# tsshield.net
KiCad netlist of a schematic drawn in EAGLE
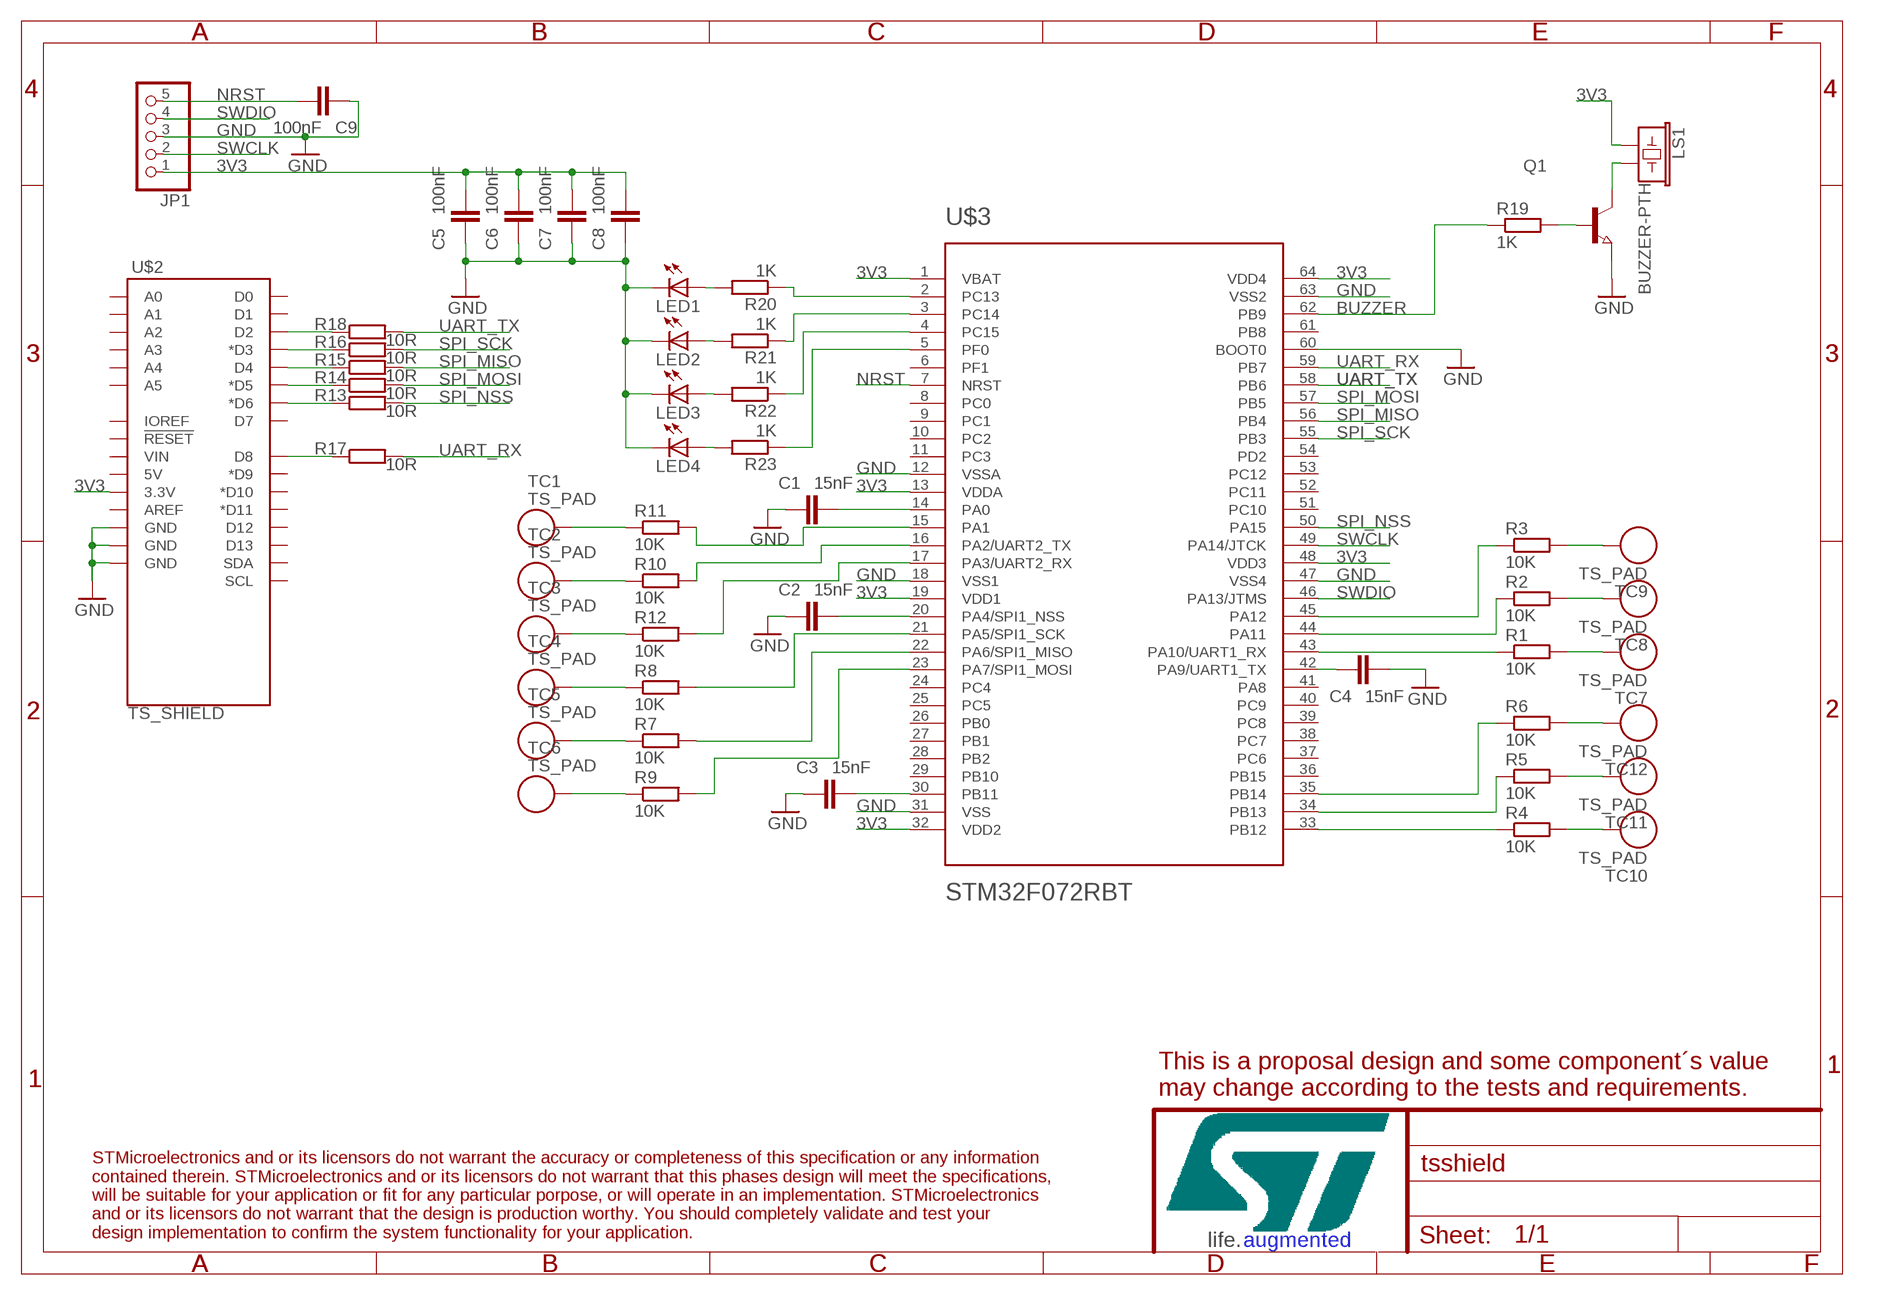
[diagram p0: schematic, sheet 1]

(export (version "E")
  (design (tool "Eeschema 10.0.6"))
  (components
    (comp (ref "C1")
      (value "15nF")
      (footprint "eagle-import:C0603")
      (libsource (lib "eagle-import") (part "CC0603"))
    )
    (comp (ref "C2")
      (value "15nF")
      (footprint "eagle-import:C0603")
      (libsource (lib "eagle-import") (part "CC0603"))
    )
    (comp (ref "C3")
      (value "15nF")
      (footprint "eagle-import:C0603")
      (libsource (lib "eagle-import") (part "CC0603"))
    )
    (comp (ref "C4")
      (value "15nF")
      (footprint "eagle-import:C0603")
      (libsource (lib "eagle-import") (part "CC0603"))
    )
    (comp (ref "C5")
      (value "100nF")
      (footprint "eagle-import:C0603")
      (libsource (lib "eagle-import") (part "CC0603"))
    )
    (comp (ref "C6")
      (value "100nF")
      (footprint "eagle-import:C0603")
      (libsource (lib "eagle-import") (part "CC0603"))
    )
    (comp (ref "C7")
      (value "100nF")
      (footprint "eagle-import:C0603")
      (libsource (lib "eagle-import") (part "CC0603"))
    )
    (comp (ref "C8")
      (value "100nF")
      (footprint "eagle-import:C0603")
      (libsource (lib "eagle-import") (part "CC0603"))
    )
    (comp (ref "C9")
      (value "100nF")
      (footprint "eagle-import:C0603")
      (libsource (lib "eagle-import") (part "CC0603"))
    )
    (comp (ref "JP1")
      (value "PINHD-1X5")
      (footprint "eagle-import:1X05")
      (libsource (lib "eagle-import") (part "PINHD-1X5"))
    )
    (comp (ref "LED1")
      (value "LED_E")
      (footprint "eagle-import:LED_1206")
      (libsource (lib "eagle-import") (part "LED_E"))
    )
    (comp (ref "LED2")
      (value "LED_E")
      (footprint "eagle-import:LED_1206")
      (libsource (lib "eagle-import") (part "LED_E"))
    )
    (comp (ref "LED3")
      (value "LED_E")
      (footprint "eagle-import:LED_1206")
      (libsource (lib "eagle-import") (part "LED_E"))
    )
    (comp (ref "LED4")
      (value "LED_E")
      (footprint "eagle-import:LED_1206")
      (libsource (lib "eagle-import") (part "LED_E"))
    )
    (comp (ref "LS1")
      (value "BUZZER-PTH")
      (footprint "eagle-import:BUZZER-12MM")
      (libsource (lib "eagle-import") (part "BUZZER-PTH"))
    )
    (comp (ref "Q1")
      (value "NPN-TRANSISTOR_SOT23")
      (footprint "eagle-import:SOT23")
      (libsource (lib "eagle-import") (part "NPN-TRANSISTOR_SOT23"))
    )
    (comp (ref "R1")
      (value "10K")
      (footprint "eagle-import:R0603")
      (libsource (lib "eagle-import") (part "RR0603"))
    )
    (comp (ref "R2")
      (value "10K")
      (footprint "eagle-import:R0603")
      (libsource (lib "eagle-import") (part "RR0603"))
    )
    (comp (ref "R3")
      (value "10K")
      (footprint "eagle-import:R0603")
      (libsource (lib "eagle-import") (part "RR0603"))
    )
    (comp (ref "R4")
      (value "10K")
      (footprint "eagle-import:R0603")
      (libsource (lib "eagle-import") (part "RR0603"))
    )
    (comp (ref "R5")
      (value "10K")
      (footprint "eagle-import:R0603")
      (libsource (lib "eagle-import") (part "RR0603"))
    )
    (comp (ref "R6")
      (value "10K")
      (footprint "eagle-import:R0603")
      (libsource (lib "eagle-import") (part "RR0603"))
    )
    (comp (ref "R7")
      (value "10K")
      (footprint "eagle-import:R0603")
      (libsource (lib "eagle-import") (part "RR0603"))
    )
    (comp (ref "R8")
      (value "10K")
      (footprint "eagle-import:R0603")
      (libsource (lib "eagle-import") (part "RR0603"))
    )
    (comp (ref "R9")
      (value "10K")
      (footprint "eagle-import:R0603")
      (libsource (lib "eagle-import") (part "RR0603"))
    )
    (comp (ref "R10")
      (value "10K")
      (footprint "eagle-import:R0603")
      (libsource (lib "eagle-import") (part "RR0603"))
    )
    (comp (ref "R11")
      (value "10K")
      (footprint "eagle-import:R0603")
      (libsource (lib "eagle-import") (part "RR0603"))
    )
    (comp (ref "R12")
      (value "10K")
      (footprint "eagle-import:R0603")
      (libsource (lib "eagle-import") (part "RR0603"))
    )
    (comp (ref "R13")
      (value "10R")
      (footprint "eagle-import:R0603")
      (libsource (lib "eagle-import") (part "RR0603"))
    )
    (comp (ref "R14")
      (value "10R")
      (footprint "eagle-import:R0603")
      (libsource (lib "eagle-import") (part "RR0603"))
    )
    (comp (ref "R15")
      (value "10R")
      (footprint "eagle-import:R0603")
      (libsource (lib "eagle-import") (part "RR0603"))
    )
    (comp (ref "R16")
      (value "10R")
      (footprint "eagle-import:R0603")
      (libsource (lib "eagle-import") (part "RR0603"))
    )
    (comp (ref "R17")
      (value "10R")
      (footprint "eagle-import:R0603")
      (libsource (lib "eagle-import") (part "RR0603"))
    )
    (comp (ref "R18")
      (value "10R")
      (footprint "eagle-import:R0603")
      (libsource (lib "eagle-import") (part "RR0603"))
    )
    (comp (ref "R19")
      (value "1K")
      (footprint "eagle-import:R0603")
      (libsource (lib "eagle-import") (part "RR0603"))
    )
    (comp (ref "R20")
      (value "1K")
      (footprint "eagle-import:R0603")
      (libsource (lib "eagle-import") (part "RR0603"))
    )
    (comp (ref "R21")
      (value "1K")
      (footprint "eagle-import:R0603")
      (libsource (lib "eagle-import") (part "RR0603"))
    )
    (comp (ref "R22")
      (value "1K")
      (footprint "eagle-import:R0603")
      (libsource (lib "eagle-import") (part "RR0603"))
    )
    (comp (ref "R23")
      (value "1K")
      (footprint "eagle-import:R0603")
      (libsource (lib "eagle-import") (part "RR0603"))
    )
    (comp (ref "TC1")
      (value "TS_PAD")
      (footprint "eagle-import:TS_PAD")
      (libsource (lib "eagle-import") (part "TS_PAD"))
    )
    (comp (ref "TC2")
      (value "TS_PAD")
      (footprint "eagle-import:TS_PAD")
      (libsource (lib "eagle-import") (part "TS_PAD"))
    )
    (comp (ref "TC3")
      (value "TS_PAD")
      (footprint "eagle-import:TS_PAD")
      (libsource (lib "eagle-import") (part "TS_PAD"))
    )
    (comp (ref "TC4")
      (value "TS_PAD")
      (footprint "eagle-import:TS_PAD")
      (libsource (lib "eagle-import") (part "TS_PAD"))
    )
    (comp (ref "TC5")
      (value "TS_PAD")
      (footprint "eagle-import:TS_PAD")
      (libsource (lib "eagle-import") (part "TS_PAD"))
    )
    (comp (ref "TC6")
      (value "TS_PAD")
      (footprint "eagle-import:TS_PAD")
      (libsource (lib "eagle-import") (part "TS_PAD"))
    )
    (comp (ref "TC7")
      (value "TS_PAD")
      (footprint "eagle-import:TS_PAD")
      (libsource (lib "eagle-import") (part "TS_PAD"))
    )
    (comp (ref "TC8")
      (value "TS_PAD")
      (footprint "eagle-import:TS_PAD")
      (libsource (lib "eagle-import") (part "TS_PAD"))
    )
    (comp (ref "TC9")
      (value "TS_PAD")
      (footprint "eagle-import:TS_PAD")
      (libsource (lib "eagle-import") (part "TS_PAD"))
    )
    (comp (ref "TC10")
      (value "TS_PAD")
      (footprint "eagle-import:TS_PAD")
      (libsource (lib "eagle-import") (part "TS_PAD"))
    )
    (comp (ref "TC11")
      (value "TS_PAD")
      (footprint "eagle-import:TS_PAD")
      (libsource (lib "eagle-import") (part "TS_PAD"))
    )
    (comp (ref "TC12")
      (value "TS_PAD")
      (footprint "eagle-import:TS_PAD")
      (libsource (lib "eagle-import") (part "TS_PAD"))
    )
    (comp (ref "U$2")
      (value "TS_SHIELD")
      (footprint "eagle-import:TS_SHIELD")
      (libsource (lib "eagle-import") (part "TS_SHIELD"))
    )
    (comp (ref "U$3")
      (value "STM32F072RBT")
      (footprint "eagle-import:TQFP64")
      (libsource (lib "eagle-import") (part "STM32F072RBT"))
    )
  )
  (nets
    (net (code "1") (name "/3V3") (class "Default")
      (node (ref "C5") (pin "1") (pinfunction "1_1") (pintype "passive"))
      (node (ref "C6") (pin "1") (pinfunction "1_1") (pintype "passive"))
      (node (ref "C7") (pin "1") (pinfunction "1_1") (pintype "passive"))
      (node (ref "C8") (pin "1") (pinfunction "1_1") (pintype "passive"))
      (node (ref "JP1") (pin "1") (pinfunction "1_1") (pintype "passive"))
      (node (ref "LS1") (pin "+") (pinfunction "1_+") (pintype "passive"))
      (node (ref "U$2") (pin "3.3V") (pinfunction "3.3V_3.3V") (pintype "bidirectional"))
      (node (ref "U$3") (pin "1") (pinfunction "VBAT_1") (pintype "bidirectional"))
      (node (ref "U$3") (pin "13") (pinfunction "VDDA_13") (pintype "bidirectional"))
      (node (ref "U$3") (pin "19") (pinfunction "VDD1_19") (pintype "bidirectional"))
      (node (ref "U$3") (pin "32") (pinfunction "VDD2_32") (pintype "bidirectional"))
      (node (ref "U$3") (pin "48") (pinfunction "VDD3_48") (pintype "bidirectional"))
      (node (ref "U$3") (pin "64") (pinfunction "VDD4_64") (pintype "bidirectional"))
    )
    (net (code "2") (name "/BUZZER") (class "Default")
      (node (ref "R19") (pin "1") (pinfunction "1_1") (pintype "passive"))
      (node (ref "U$3") (pin "62") (pinfunction "PB9_62") (pintype "bidirectional"))
    )
    (net (code "3") (name "/NRST") (class "Default")
      (node (ref "C9") (pin "1") (pinfunction "1_1") (pintype "passive"))
      (node (ref "JP1") (pin "5") (pinfunction "5_5") (pintype "passive"))
      (node (ref "U$3") (pin "7") (pinfunction "NRST_7") (pintype "bidirectional"))
    )
    (net (code "4") (name "/SPI_MISO") (class "Default")
      (node (ref "R15") (pin "2") (pinfunction "2_2") (pintype "passive"))
      (node (ref "U$3") (pin "56") (pinfunction "PB4_56") (pintype "bidirectional"))
    )
    (net (code "5") (name "/SPI_MOSI") (class "Default")
      (node (ref "R14") (pin "2") (pinfunction "2_2") (pintype "passive"))
      (node (ref "U$3") (pin "57") (pinfunction "PB5_57") (pintype "bidirectional"))
    )
    (net (code "6") (name "/SPI_NSS") (class "Default")
      (node (ref "R13") (pin "2") (pinfunction "2_2") (pintype "passive"))
      (node (ref "U$3") (pin "50") (pinfunction "PA15_50") (pintype "bidirectional"))
    )
    (net (code "7") (name "/SPI_SCK") (class "Default")
      (node (ref "R16") (pin "2") (pinfunction "2_2") (pintype "passive"))
      (node (ref "U$3") (pin "55") (pinfunction "PB3_55") (pintype "bidirectional"))
    )
    (net (code "8") (name "/SWCLK") (class "Default")
      (node (ref "JP1") (pin "2") (pinfunction "2_2") (pintype "passive"))
      (node (ref "U$3") (pin "49") (pinfunction "PA14/JTCK_49") (pintype "bidirectional"))
    )
    (net (code "9") (name "/SWDIO") (class "Default")
      (node (ref "JP1") (pin "4") (pinfunction "4_4") (pintype "passive"))
      (node (ref "U$3") (pin "46") (pinfunction "PA13/JTMS_46") (pintype "bidirectional"))
    )
    (net (code "10") (name "/UART_RX") (class "Default")
      (node (ref "R17") (pin "2") (pinfunction "2_2") (pintype "passive"))
      (node (ref "U$3") (pin "59") (pinfunction "PB7_59") (pintype "bidirectional"))
    )
    (net (code "11") (name "/UART_TX") (class "Default")
      (node (ref "R18") (pin "2") (pinfunction "2_2") (pintype "passive"))
      (node (ref "U$3") (pin "58") (pinfunction "PB6_58") (pintype "bidirectional"))
    )
    (net (code "12") (name "GND") (class "Default")
      (node (ref "C1") (pin "2") (pinfunction "2_2") (pintype "passive"))
      (node (ref "C2") (pin "2") (pinfunction "2_2") (pintype "passive"))
      (node (ref "C3") (pin "2") (pinfunction "2_2") (pintype "passive"))
      (node (ref "C4") (pin "1") (pinfunction "1_1") (pintype "passive"))
      (node (ref "C5") (pin "2") (pinfunction "2_2") (pintype "passive"))
      (node (ref "C6") (pin "2") (pinfunction "2_2") (pintype "passive"))
      (node (ref "C7") (pin "2") (pinfunction "2_2") (pintype "passive"))
      (node (ref "C8") (pin "2") (pinfunction "2_2") (pintype "passive"))
      (node (ref "C9") (pin "2") (pinfunction "2_2") (pintype "passive"))
      (node (ref "JP1") (pin "3") (pinfunction "3_3") (pintype "passive"))
      (node (ref "LED1") (pin "C") (pinfunction "C_C") (pintype "passive"))
      (node (ref "LED2") (pin "C") (pinfunction "C_C") (pintype "passive"))
      (node (ref "LED3") (pin "C") (pinfunction "C_C") (pintype "passive"))
      (node (ref "LED4") (pin "C") (pinfunction "C_C") (pintype "passive"))
      (node (ref "Q1") (pin "2") (pinfunction "E_2") (pintype "passive"))
      (node (ref "U$2") (pin "GND@1") (pinfunction "GND_GND@1") (pintype "bidirectional"))
      (node (ref "U$2") (pin "GND@2") (pinfunction "GND_GND@2") (pintype "bidirectional"))
      (node (ref "U$2") (pin "GND@3") (pinfunction "GND_GND@3") (pintype "bidirectional"))
      (node (ref "U$3") (pin "12") (pinfunction "VSSA_12") (pintype "bidirectional"))
      (node (ref "U$3") (pin "18") (pinfunction "VSS1_18") (pintype "bidirectional"))
      (node (ref "U$3") (pin "31") (pinfunction "VSS_31") (pintype "bidirectional"))
      (node (ref "U$3") (pin "47") (pinfunction "VSS4_47") (pintype "bidirectional"))
      (node (ref "U$3") (pin "60") (pinfunction "BOOT0_60") (pintype "bidirectional"))
      (node (ref "U$3") (pin "63") (pinfunction "VSS2_63") (pintype "bidirectional"))
    )
    (net (code "13") (name "Net-(LED1-PadA)") (class "Default")
      (node (ref "LED1") (pin "A") (pinfunction "A_A") (pintype "passive"))
      (node (ref "R20") (pin "2") (pinfunction "2_2") (pintype "passive"))
    )
    (net (code "14") (name "Net-(LED2-PadA)") (class "Default")
      (node (ref "LED2") (pin "A") (pinfunction "A_A") (pintype "passive"))
      (node (ref "R21") (pin "2") (pinfunction "2_2") (pintype "passive"))
    )
    (net (code "15") (name "Net-(LED3-PadA)") (class "Default")
      (node (ref "LED3") (pin "A") (pinfunction "A_A") (pintype "passive"))
      (node (ref "R22") (pin "2") (pinfunction "2_2") (pintype "passive"))
    )
    (net (code "16") (name "Net-(LED4-PadA)") (class "Default")
      (node (ref "LED4") (pin "A") (pinfunction "A_A") (pintype "passive"))
      (node (ref "R23") (pin "2") (pinfunction "2_2") (pintype "passive"))
    )
    (net (code "17") (name "Net-(LS1-2)") (class "Default")
      (node (ref "LS1") (pin "-") (pinfunction "2_-") (pintype "passive"))
      (node (ref "Q1") (pin "3") (pinfunction "C_3") (pintype "passive"))
    )
    (net (code "18") (name "Net-(Q1-B)") (class "Default")
      (node (ref "Q1") (pin "1") (pinfunction "B_1") (pintype "passive"))
      (node (ref "R19") (pin "2") (pinfunction "2_2") (pintype "passive"))
    )
    (net (code "19") (name "Net-(R15-Pad1)") (class "Default")
      (node (ref "R15") (pin "1") (pinfunction "1_1") (pintype "passive"))
      (node (ref "U$2") (pin "D4") (pinfunction "D4_D4") (pintype "bidirectional"))
    )
    (net (code "20") (name "Net-(R17-Pad1)") (class "Default")
      (node (ref "R17") (pin "1") (pinfunction "1_1") (pintype "passive"))
      (node (ref "U$2") (pin "D8") (pinfunction "D8_D8") (pintype "bidirectional"))
    )
    (net (code "21") (name "Net-(R18-Pad1)") (class "Default")
      (node (ref "R18") (pin "1") (pinfunction "1_1") (pintype "passive"))
      (node (ref "U$2") (pin "D2") (pinfunction "D2_D2") (pintype "bidirectional"))
    )
    (net (code "22") (name "Net-(TC1-P$1)") (class "Default")
      (node (ref "R11") (pin "1") (pinfunction "1_1") (pintype "passive"))
      (node (ref "TC1") (pin "1") (pinfunction "P$1_1") (pintype "bidirectional"))
    )
    (net (code "23") (name "Net-(TC2-P$1)") (class "Default")
      (node (ref "R10") (pin "1") (pinfunction "1_1") (pintype "passive"))
      (node (ref "TC2") (pin "1") (pinfunction "P$1_1") (pintype "bidirectional"))
    )
    (net (code "24") (name "Net-(TC3-P$1)") (class "Default")
      (node (ref "R12") (pin "1") (pinfunction "1_1") (pintype "passive"))
      (node (ref "TC3") (pin "1") (pinfunction "P$1_1") (pintype "bidirectional"))
    )
    (net (code "25") (name "Net-(TC4-P$1)") (class "Default")
      (node (ref "R8") (pin "1") (pinfunction "1_1") (pintype "passive"))
      (node (ref "TC4") (pin "1") (pinfunction "P$1_1") (pintype "bidirectional"))
    )
    (net (code "26") (name "Net-(TC5-P$1)") (class "Default")
      (node (ref "R7") (pin "1") (pinfunction "1_1") (pintype "passive"))
      (node (ref "TC5") (pin "1") (pinfunction "P$1_1") (pintype "bidirectional"))
    )
    (net (code "27") (name "Net-(TC6-P$1)") (class "Default")
      (node (ref "R9") (pin "1") (pinfunction "1_1") (pintype "passive"))
      (node (ref "TC6") (pin "1") (pinfunction "P$1_1") (pintype "bidirectional"))
    )
    (net (code "28") (name "Net-(TC7-P$1)") (class "Default")
      (node (ref "R1") (pin "2") (pinfunction "2_2") (pintype "passive"))
      (node (ref "TC7") (pin "1") (pinfunction "P$1_1") (pintype "bidirectional"))
    )
    (net (code "29") (name "Net-(TC8-P$1)") (class "Default")
      (node (ref "R2") (pin "2") (pinfunction "2_2") (pintype "passive"))
      (node (ref "TC8") (pin "1") (pinfunction "P$1_1") (pintype "bidirectional"))
    )
    (net (code "30") (name "Net-(TC9-P$1)") (class "Default")
      (node (ref "R3") (pin "2") (pinfunction "2_2") (pintype "passive"))
      (node (ref "TC9") (pin "1") (pinfunction "P$1_1") (pintype "bidirectional"))
    )
    (net (code "31") (name "Net-(TC10-P$1)") (class "Default")
      (node (ref "R4") (pin "2") (pinfunction "2_2") (pintype "passive"))
      (node (ref "TC10") (pin "1") (pinfunction "P$1_1") (pintype "bidirectional"))
    )
    (net (code "32") (name "Net-(TC11-P$1)") (class "Default")
      (node (ref "R5") (pin "2") (pinfunction "2_2") (pintype "passive"))
      (node (ref "TC11") (pin "1") (pinfunction "P$1_1") (pintype "bidirectional"))
    )
    (net (code "33") (name "Net-(TC12-P$1)") (class "Default")
      (node (ref "R6") (pin "2") (pinfunction "2_2") (pintype "passive"))
      (node (ref "TC12") (pin "1") (pinfunction "P$1_1") (pintype "bidirectional"))
    )
    (net (code "34") (name "Net-(U$2-*D3)") (class "Default")
      (node (ref "R16") (pin "1") (pinfunction "1_1") (pintype "passive"))
      (node (ref "U$2") (pin "D3") (pinfunction "*D3_D3") (pintype "bidirectional"))
    )
    (net (code "35") (name "Net-(U$2-*D5)") (class "Default")
      (node (ref "R14") (pin "1") (pinfunction "1_1") (pintype "passive"))
      (node (ref "U$2") (pin "D5") (pinfunction "*D5_D5") (pintype "bidirectional"))
    )
    (net (code "36") (name "Net-(U$2-*D6)") (class "Default")
      (node (ref "R13") (pin "1") (pinfunction "1_1") (pintype "passive"))
      (node (ref "U$2") (pin "D6") (pinfunction "*D6_D6") (pintype "bidirectional"))
    )
    (net (code "37") (name "Net-(U$3-PA0)") (class "Default")
      (node (ref "C1") (pin "1") (pinfunction "1_1") (pintype "passive"))
      (node (ref "U$3") (pin "14") (pinfunction "PA0_14") (pintype "bidirectional"))
    )
    (net (code "38") (name "Net-(U$3-PA1)") (class "Default")
      (node (ref "R11") (pin "2") (pinfunction "2_2") (pintype "passive"))
      (node (ref "U$3") (pin "15") (pinfunction "PA1_15") (pintype "bidirectional"))
    )
    (net (code "39") (name "Net-(U$3-PA2{slash}UART2_TX)") (class "Default")
      (node (ref "R10") (pin "2") (pinfunction "2_2") (pintype "passive"))
      (node (ref "U$3") (pin "16") (pinfunction "PA2/UART2_TX_16") (pintype "bidirectional"))
    )
    (net (code "40") (name "Net-(U$3-PA3{slash}UART2_RX)") (class "Default")
      (node (ref "R12") (pin "2") (pinfunction "2_2") (pintype "passive"))
      (node (ref "U$3") (pin "17") (pinfunction "PA3/UART2_RX_17") (pintype "bidirectional"))
    )
    (net (code "41") (name "Net-(U$3-PA4{slash}SPI1_NSS)") (class "Default")
      (node (ref "C2") (pin "1") (pinfunction "1_1") (pintype "passive"))
      (node (ref "U$3") (pin "20") (pinfunction "PA4/SPI1_NSS_20") (pintype "bidirectional"))
    )
    (net (code "42") (name "Net-(U$3-PA5{slash}SPI1_SCK)") (class "Default")
      (node (ref "R8") (pin "2") (pinfunction "2_2") (pintype "passive"))
      (node (ref "U$3") (pin "21") (pinfunction "PA5/SPI1_SCK_21") (pintype "bidirectional"))
    )
    (net (code "43") (name "Net-(U$3-PA6{slash}SPI1_MISO)") (class "Default")
      (node (ref "R7") (pin "2") (pinfunction "2_2") (pintype "passive"))
      (node (ref "U$3") (pin "22") (pinfunction "PA6/SPI1_MISO_22") (pintype "bidirectional"))
    )
    (net (code "44") (name "Net-(U$3-PA7{slash}SPI1_MOSI)") (class "Default")
      (node (ref "R9") (pin "2") (pinfunction "2_2") (pintype "passive"))
      (node (ref "U$3") (pin "23") (pinfunction "PA7/SPI1_MOSI_23") (pintype "bidirectional"))
    )
    (net (code "45") (name "Net-(U$3-PA9{slash}UART1_TX)") (class "Default")
      (node (ref "C4") (pin "2") (pinfunction "2_2") (pintype "passive"))
      (node (ref "U$3") (pin "42") (pinfunction "PA9/UART1_TX_42") (pintype "bidirectional"))
    )
    (net (code "46") (name "Net-(U$3-PA10{slash}UART1_RX)") (class "Default")
      (node (ref "R1") (pin "1") (pinfunction "1_1") (pintype "passive"))
      (node (ref "U$3") (pin "43") (pinfunction "PA10/UART1_RX_43") (pintype "bidirectional"))
    )
    (net (code "47") (name "Net-(U$3-PA11)") (class "Default")
      (node (ref "R2") (pin "1") (pinfunction "1_1") (pintype "passive"))
      (node (ref "U$3") (pin "44") (pinfunction "PA11_44") (pintype "bidirectional"))
    )
    (net (code "48") (name "Net-(U$3-PA12)") (class "Default")
      (node (ref "R3") (pin "1") (pinfunction "1_1") (pintype "passive"))
      (node (ref "U$3") (pin "45") (pinfunction "PA12_45") (pintype "bidirectional"))
    )
    (net (code "49") (name "Net-(U$3-PB11)") (class "Default")
      (node (ref "C3") (pin "1") (pinfunction "1_1") (pintype "passive"))
      (node (ref "U$3") (pin "30") (pinfunction "PB11_30") (pintype "bidirectional"))
    )
    (net (code "50") (name "Net-(U$3-PB12)") (class "Default")
      (node (ref "R4") (pin "1") (pinfunction "1_1") (pintype "passive"))
      (node (ref "U$3") (pin "33") (pinfunction "PB12_33") (pintype "bidirectional"))
    )
    (net (code "51") (name "Net-(U$3-PB13)") (class "Default")
      (node (ref "R5") (pin "1") (pinfunction "1_1") (pintype "passive"))
      (node (ref "U$3") (pin "34") (pinfunction "PB13_34") (pintype "bidirectional"))
    )
    (net (code "52") (name "Net-(U$3-PB14)") (class "Default")
      (node (ref "R6") (pin "1") (pinfunction "1_1") (pintype "passive"))
      (node (ref "U$3") (pin "35") (pinfunction "PB14_35") (pintype "bidirectional"))
    )
    (net (code "53") (name "Net-(U$3-PC13)") (class "Default")
      (node (ref "R20") (pin "1") (pinfunction "1_1") (pintype "passive"))
      (node (ref "U$3") (pin "2") (pinfunction "PC13_2") (pintype "bidirectional"))
    )
    (net (code "54") (name "Net-(U$3-PC14)") (class "Default")
      (node (ref "R21") (pin "1") (pinfunction "1_1") (pintype "passive"))
      (node (ref "U$3") (pin "3") (pinfunction "PC14_3") (pintype "bidirectional"))
    )
    (net (code "55") (name "Net-(U$3-PC15)") (class "Default")
      (node (ref "R22") (pin "1") (pinfunction "1_1") (pintype "passive"))
      (node (ref "U$3") (pin "4") (pinfunction "PC15_4") (pintype "bidirectional"))
    )
    (net (code "56") (name "Net-(U$3-PF0)") (class "Default")
      (node (ref "R23") (pin "1") (pinfunction "1_1") (pintype "passive"))
      (node (ref "U$3") (pin "5") (pinfunction "PF0_5") (pintype "bidirectional"))
    )
    (net (code "57") (name "unconnected-(U$2-*D9-PadD9)") (class "Default")
      (node (ref "U$2") (pin "D9") (pinfunction "*D9_D9") (pintype "bidirectional"))
    )
    (net (code "58") (name "unconnected-(U$2-*D10-PadD10)") (class "Default")
      (node (ref "U$2") (pin "D10") (pinfunction "*D10_D10") (pintype "bidirectional"))
    )
    (net (code "59") (name "unconnected-(U$2-*D11-PadD11)") (class "Default")
      (node (ref "U$2") (pin "D11") (pinfunction "*D11_D11") (pintype "bidirectional"))
    )
    (net (code "60") (name "unconnected-(U$2-Pad5V)") (class "Default")
      (node (ref "U$2") (pin "5V") (pinfunction "5V_5V") (pintype "bidirectional"))
    )
    (net (code "61") (name "unconnected-(U$2-PadA0)") (class "Default")
      (node (ref "U$2") (pin "A0") (pinfunction "A0_A0") (pintype "bidirectional"))
    )
    (net (code "62") (name "unconnected-(U$2-PadA1)") (class "Default")
      (node (ref "U$2") (pin "A1") (pinfunction "A1_A1") (pintype "bidirectional"))
    )
    (net (code "63") (name "unconnected-(U$2-PadA2)") (class "Default")
      (node (ref "U$2") (pin "A2") (pinfunction "A2_A2") (pintype "bidirectional"))
    )
    (net (code "64") (name "unconnected-(U$2-PadA3)") (class "Default")
      (node (ref "U$2") (pin "A3") (pinfunction "A3_A3") (pintype "bidirectional"))
    )
    (net (code "65") (name "unconnected-(U$2-PadA4)") (class "Default")
      (node (ref "U$2") (pin "A4") (pinfunction "A4_A4") (pintype "bidirectional"))
    )
    (net (code "66") (name "unconnected-(U$2-PadA5)") (class "Default")
      (node (ref "U$2") (pin "A5") (pinfunction "A5_A5") (pintype "bidirectional"))
    )
    (net (code "67") (name "unconnected-(U$2-PadAREF)") (class "Default")
      (node (ref "U$2") (pin "AREF") (pinfunction "AREF_AREF") (pintype "bidirectional"))
    )
    (net (code "68") (name "unconnected-(U$2-PadD0)") (class "Default")
      (node (ref "U$2") (pin "D0") (pinfunction "D0_D0") (pintype "bidirectional"))
    )
    (net (code "69") (name "unconnected-(U$2-PadD1)") (class "Default")
      (node (ref "U$2") (pin "D1") (pinfunction "D1_D1") (pintype "bidirectional"))
    )
    (net (code "70") (name "unconnected-(U$2-PadD7)") (class "Default")
      (node (ref "U$2") (pin "D7") (pinfunction "D7_D7") (pintype "bidirectional"))
    )
    (net (code "71") (name "unconnected-(U$2-PadD12)") (class "Default")
      (node (ref "U$2") (pin "D12") (pinfunction "D12_D12") (pintype "bidirectional"))
    )
    (net (code "72") (name "unconnected-(U$2-PadD13)") (class "Default")
      (node (ref "U$2") (pin "D13") (pinfunction "D13_D13") (pintype "bidirectional"))
    )
    (net (code "73") (name "unconnected-(U$2-PadIOREF)") (class "Default")
      (node (ref "U$2") (pin "IOREF") (pinfunction "IOREF_IOREF") (pintype "bidirectional"))
    )
    (net (code "74") (name "unconnected-(U$2-PadSCL)") (class "Default")
      (node (ref "U$2") (pin "SCL") (pinfunction "SCL_SCL") (pintype "bidirectional"))
    )
    (net (code "75") (name "unconnected-(U$2-PadSDA)") (class "Default")
      (node (ref "U$2") (pin "SDA") (pinfunction "SDA_SDA") (pintype "bidirectional"))
    )
    (net (code "76") (name "unconnected-(U$2-PadVIN)") (class "Default")
      (node (ref "U$2") (pin "VIN") (pinfunction "VIN_VIN") (pintype "bidirectional"))
    )
    (net (code "77") (name "unconnected-(U$2-~{RESET}-PadRESET@1)") (class "Default")
      (node (ref "U$2") (pin "RESET@1") (pinfunction "~{RESET}_RESET@1") (pintype "bidirectional"))
    )
    (net (code "78") (name "unconnected-(U$3-PA8-Pad41)") (class "Default")
      (node (ref "U$3") (pin "41") (pinfunction "PA8_41") (pintype "bidirectional"))
    )
    (net (code "79") (name "unconnected-(U$3-PB0-Pad26)") (class "Default")
      (node (ref "U$3") (pin "26") (pinfunction "PB0_26") (pintype "bidirectional"))
    )
    (net (code "80") (name "unconnected-(U$3-PB1-Pad27)") (class "Default")
      (node (ref "U$3") (pin "27") (pinfunction "PB1_27") (pintype "bidirectional"))
    )
    (net (code "81") (name "unconnected-(U$3-PB2-Pad28)") (class "Default")
      (node (ref "U$3") (pin "28") (pinfunction "PB2_28") (pintype "bidirectional"))
    )
    (net (code "82") (name "unconnected-(U$3-PB8-Pad61)") (class "Default")
      (node (ref "U$3") (pin "61") (pinfunction "PB8_61") (pintype "bidirectional"))
    )
    (net (code "83") (name "unconnected-(U$3-PB10-Pad29)") (class "Default")
      (node (ref "U$3") (pin "29") (pinfunction "PB10_29") (pintype "bidirectional"))
    )
    (net (code "84") (name "unconnected-(U$3-PB15-Pad36)") (class "Default")
      (node (ref "U$3") (pin "36") (pinfunction "PB15_36") (pintype "bidirectional"))
    )
    (net (code "85") (name "unconnected-(U$3-PC0-Pad8)") (class "Default")
      (node (ref "U$3") (pin "8") (pinfunction "PC0_8") (pintype "bidirectional"))
    )
    (net (code "86") (name "unconnected-(U$3-PC1-Pad9)") (class "Default")
      (node (ref "U$3") (pin "9") (pinfunction "PC1_9") (pintype "bidirectional"))
    )
    (net (code "87") (name "unconnected-(U$3-PC2-Pad10)") (class "Default")
      (node (ref "U$3") (pin "10") (pinfunction "PC2_10") (pintype "bidirectional"))
    )
    (net (code "88") (name "unconnected-(U$3-PC3-Pad11)") (class "Default")
      (node (ref "U$3") (pin "11") (pinfunction "PC3_11") (pintype "bidirectional"))
    )
    (net (code "89") (name "unconnected-(U$3-PC4-Pad24)") (class "Default")
      (node (ref "U$3") (pin "24") (pinfunction "PC4_24") (pintype "bidirectional"))
    )
    (net (code "90") (name "unconnected-(U$3-PC5-Pad25)") (class "Default")
      (node (ref "U$3") (pin "25") (pinfunction "PC5_25") (pintype "bidirectional"))
    )
    (net (code "91") (name "unconnected-(U$3-PC6-Pad37)") (class "Default")
      (node (ref "U$3") (pin "37") (pinfunction "PC6_37") (pintype "bidirectional"))
    )
    (net (code "92") (name "unconnected-(U$3-PC7-Pad38)") (class "Default")
      (node (ref "U$3") (pin "38") (pinfunction "PC7_38") (pintype "bidirectional"))
    )
    (net (code "93") (name "unconnected-(U$3-PC8-Pad39)") (class "Default")
      (node (ref "U$3") (pin "39") (pinfunction "PC8_39") (pintype "bidirectional"))
    )
    (net (code "94") (name "unconnected-(U$3-PC9-Pad40)") (class "Default")
      (node (ref "U$3") (pin "40") (pinfunction "PC9_40") (pintype "bidirectional"))
    )
    (net (code "95") (name "unconnected-(U$3-PC10-Pad51)") (class "Default")
      (node (ref "U$3") (pin "51") (pinfunction "PC10_51") (pintype "bidirectional"))
    )
    (net (code "96") (name "unconnected-(U$3-PC11-Pad52)") (class "Default")
      (node (ref "U$3") (pin "52") (pinfunction "PC11_52") (pintype "bidirectional"))
    )
    (net (code "97") (name "unconnected-(U$3-PC12-Pad53)") (class "Default")
      (node (ref "U$3") (pin "53") (pinfunction "PC12_53") (pintype "bidirectional"))
    )
    (net (code "98") (name "unconnected-(U$3-PD2-Pad54)") (class "Default")
      (node (ref "U$3") (pin "54") (pinfunction "PD2_54") (pintype "bidirectional"))
    )
    (net (code "99") (name "unconnected-(U$3-PF1-Pad6)") (class "Default")
      (node (ref "U$3") (pin "6") (pinfunction "PF1_6") (pintype "bidirectional"))
    )
  )
)
